# USB.net
KiCad netlist of a schematic drawn in Altium Designer
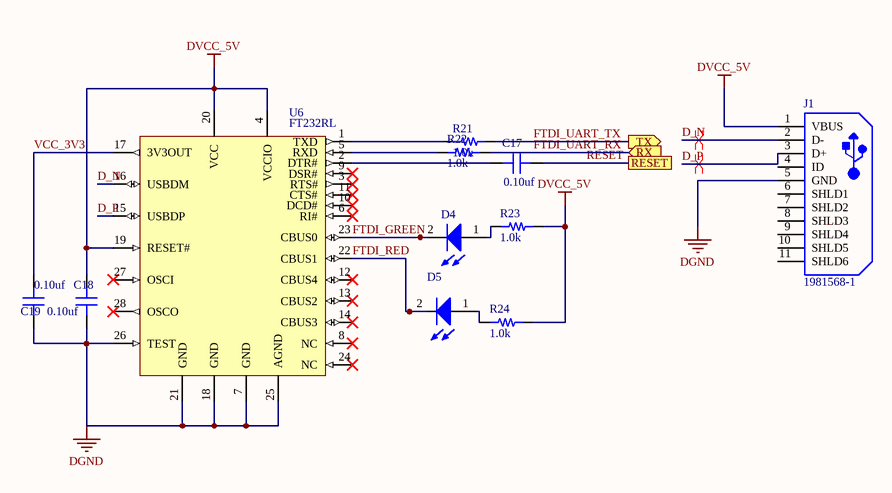
[diagram p0: USB.SchDoc]

(export (version "E")
  (design (tool "Eeschema 10.0.6"))
  (components
    (comp (ref "C17")
      (value "0.10uf")
      (footprint "CAP 0603/1608")
      (fields
        (field (name "Comment") "Capacitor MLCC 0.10uf 25V CAP 0603/1608")
        (field (name "CREATED_BY") "Nick Mah")
      )
      (libsource (lib "Altium-Lib") (part "Capacitor"))
    )
    (comp (ref "C18")
      (value "0.10uf")
      (footprint "CAP 0603/1608")
      (fields
        (field (name "Comment") "Capacitor MLCC 0.10uf 25V CAP 0603/1608")
        (field (name "CREATED_BY") "Nick Mah")
      )
      (libsource (lib "Altium-Lib") (part "Capacitor"))
    )
    (comp (ref "C19")
      (value "0.10uf")
      (footprint "CAP 0603/1608")
      (fields
        (field (name "Comment") "Capacitor MLCC 0.10uf 25V CAP 0603/1608")
        (field (name "CREATED_BY") "Nick Mah")
      )
      (libsource (lib "Altium-Lib") (part "Capacitor"))
    )
    (comp (ref "D4") (value "~") (footprint "0805_LED") (libsource (lib "Altium-Lib") (part "LED")))
    (comp (ref "D5") (value "~") (footprint "0805_LED") (libsource (lib "Altium-Lib") (part "LED")))
    (comp (ref "J1")
      (value "1981568-1")
      (footprint "TECO-1981568-5_V")
      (description "USB Micro Type B")
      (fields (field (name "CREATED_BY") "Aiku"))
      (libsource (lib "Altium-Lib") (part "USB-5-6SHLD"))
    )
    (comp (ref "R21")
      (value "1.0k")
      (footprint "RES 0603/1608")
      (fields
        (field (name "TOLERANCE") "5%")
        (field (name "POWER") "1/10W")
        (field (name "Comment") "Resistor 1.0k 0603 1/10W 5%")
        (field (name "CREATED_BY") "Nick Mah")
      )
      (libsource (lib "Altium-Lib") (part "Resistor"))
    )
    (comp (ref "R22")
      (value "1.0k")
      (footprint "RES 0603/1608")
      (fields
        (field (name "TOLERANCE") "5%")
        (field (name "POWER") "1/10W")
        (field (name "Comment") "Resistor 1.0k 0603 1/10W 5%")
        (field (name "CREATED_BY") "Nick Mah")
      )
      (libsource (lib "Altium-Lib") (part "Resistor"))
    )
    (comp (ref "R23")
      (value "1.0k")
      (footprint "RES 0603/1608")
      (fields
        (field (name "TOLERANCE") "5%")
        (field (name "POWER") "1/10W")
        (field (name "Comment") "Resistor 1.0k 0603 1/10W 5%")
        (field (name "CREATED_BY") "Nick Mah")
      )
      (libsource (lib "Altium-Lib") (part "Resistor"))
    )
    (comp (ref "R24")
      (value "1.0k")
      (footprint "RES 0603/1608")
      (fields
        (field (name "TOLERANCE") "5%")
        (field (name "POWER") "1/10W")
        (field (name "Comment") "Resistor 1.0k 0603 1/10W 5%")
        (field (name "CREATED_BY") "Nick Mah")
      )
      (libsource (lib "Altium-Lib") (part "Resistor"))
    )
    (comp (ref "U6")
      (value "FT232RL")
      (footprint "SSOP-28")
      (fields (field (name "CREATED_BY") "Kyle"))
      (libsource (lib "Altium-Lib") (part "FT232RL"))
    )
  )
  (nets
    (net (code "1") (name "/D_N") (class "Default")
      (node (ref "J1") (pin "2") (pinfunction "D-_2") (pintype "passive"))
      (node (ref "U6") (pin "16") (pinfunction "USBDM_16") (pintype "bidirectional"))
    )
    (net (code "2") (name "/D_P") (class "Default")
      (node (ref "J1") (pin "3") (pinfunction "D+_3") (pintype "passive"))
      (node (ref "U6") (pin "15") (pinfunction "USBDP_15") (pintype "bidirectional"))
    )
    (net (code "3") (name "/FTDI_GREEN") (class "Default")
      (node (ref "D4") (pin "2") (pinfunction "K_2") (pintype "passive"))
      (node (ref "U6") (pin "23") (pinfunction "CBUS0_23") (pintype "bidirectional"))
    )
    (net (code "4") (name "/FTDI_RED") (class "Default")
      (node (ref "D5") (pin "2") (pinfunction "K_2") (pintype "passive"))
      (node (ref "U6") (pin "22") (pinfunction "CBUS1_22") (pintype "bidirectional"))
    )
    (net (code "5") (name "/FTDI_UART_RX") (class "Default")
      (node (ref "R22") (pin "2") (pinfunction "2_2") (pintype "passive"))
    )
    (net (code "6") (name "/FTDI_UART_TX") (class "Default")
      (node (ref "R21") (pin "2") (pinfunction "2_2") (pintype "passive"))
    )
    (net (code "7") (name "/RESET") (class "Default")
      (node (ref "C17") (pin "2") (pinfunction "2_2") (pintype "passive"))
    )
    (net (code "8") (name "/VCC_3V3") (class "Default")
      (node (ref "C19") (pin "2") (pinfunction "2_2") (pintype "passive"))
      (node (ref "U6") (pin "17") (pinfunction "3V3OUT_17") (pintype "output"))
    )
    (net (code "9") (name "DGND") (class "Default")
      (node (ref "C18") (pin "1") (pinfunction "1_1") (pintype "passive"))
      (node (ref "C19") (pin "1") (pinfunction "1_1") (pintype "passive"))
      (node (ref "J1") (pin "5") (pinfunction "GND_5") (pintype "passive"))
      (node (ref "U6") (pin "18") (pinfunction "GND_18") (pintype "passive"))
      (node (ref "U6") (pin "21") (pinfunction "GND_21") (pintype "passive"))
      (node (ref "U6") (pin "25") (pinfunction "AGND_25") (pintype "passive"))
      (node (ref "U6") (pin "26") (pinfunction "TEST_26") (pintype "input"))
      (node (ref "U6") (pin "7") (pinfunction "GND_7") (pintype "passive"))
    )
    (net (code "10") (name "DVCC_5V") (class "Default")
      (node (ref "C18") (pin "2") (pinfunction "2_2") (pintype "passive"))
      (node (ref "J1") (pin "1") (pinfunction "VBUS_1") (pintype "passive"))
      (node (ref "R23") (pin "2") (pinfunction "2_2") (pintype "passive"))
      (node (ref "R24") (pin "2") (pinfunction "2_2") (pintype "passive"))
      (node (ref "U6") (pin "19") (pinfunction "RESET#_19") (pintype "input"))
      (node (ref "U6") (pin "20") (pinfunction "VCC_20") (pintype "passive"))
      (node (ref "U6") (pin "4") (pinfunction "VCCIO_4") (pintype "passive"))
    )
    (net (code "11") (name "Net-(D4-A)") (class "Default")
      (node (ref "D4") (pin "1") (pinfunction "A_1") (pintype "passive"))
      (node (ref "R23") (pin "1") (pinfunction "1_1") (pintype "passive"))
    )
    (net (code "12") (name "Net-(D5-A)") (class "Default")
      (node (ref "D5") (pin "1") (pinfunction "A_1") (pintype "passive"))
      (node (ref "R24") (pin "1") (pinfunction "1_1") (pintype "passive"))
    )
    (net (code "13") (name "Net-(U6-DTR#)") (class "Default")
      (node (ref "C17") (pin "1") (pinfunction "1_1") (pintype "passive"))
      (node (ref "U6") (pin "2") (pinfunction "DTR#_2") (pintype "output"))
    )
    (net (code "14") (name "Net-(U6-RXD)") (class "Default")
      (node (ref "R22") (pin "1") (pinfunction "1_1") (pintype "passive"))
      (node (ref "U6") (pin "5") (pinfunction "RXD_5") (pintype "input"))
    )
    (net (code "15") (name "Net-(U6-TXD)") (class "Default")
      (node (ref "R21") (pin "1") (pinfunction "1_1") (pintype "passive"))
      (node (ref "U6") (pin "1") (pinfunction "TXD_1") (pintype "output"))
    )
    (net (code "16") (name "unconnected-(J1-ID-Pad4)") (class "Default")
      (node (ref "J1") (pin "4") (pinfunction "ID_4") (pintype "passive"))
    )
    (net (code "17") (name "unconnected-(J1-SHLD1-Pad6)") (class "Default")
      (node (ref "J1") (pin "6") (pinfunction "SHLD1_6") (pintype "passive"))
    )
    (net (code "18") (name "unconnected-(J1-SHLD2-Pad7)") (class "Default")
      (node (ref "J1") (pin "7") (pinfunction "SHLD2_7") (pintype "passive"))
    )
    (net (code "19") (name "unconnected-(J1-SHLD3-Pad8)") (class "Default")
      (node (ref "J1") (pin "8") (pinfunction "SHLD3_8") (pintype "passive"))
    )
    (net (code "20") (name "unconnected-(J1-SHLD4-Pad9)") (class "Default")
      (node (ref "J1") (pin "9") (pinfunction "SHLD4_9") (pintype "passive"))
    )
    (net (code "21") (name "unconnected-(J1-SHLD5-Pad10)") (class "Default")
      (node (ref "J1") (pin "10") (pinfunction "SHLD5_10") (pintype "passive"))
    )
    (net (code "22") (name "unconnected-(J1-SHLD6-Pad11)") (class "Default")
      (node (ref "J1") (pin "11") (pinfunction "SHLD6_11") (pintype "passive"))
    )
    (net (code "23") (name "unconnected-(U6-CBUS2-Pad13)") (class "Default")
      (node (ref "U6") (pin "13") (pinfunction "CBUS2_13") (pintype "bidirectional+no_connect"))
    )
    (net (code "24") (name "unconnected-(U6-CBUS3-Pad14)") (class "Default")
      (node (ref "U6") (pin "14") (pinfunction "CBUS3_14") (pintype "bidirectional+no_connect"))
    )
    (net (code "25") (name "unconnected-(U6-CBUS4-Pad12)") (class "Default")
      (node (ref "U6") (pin "12") (pinfunction "CBUS4_12") (pintype "bidirectional+no_connect"))
    )
    (net (code "26") (name "unconnected-(U6-CTS#-Pad11)") (class "Default")
      (node (ref "U6") (pin "11") (pinfunction "CTS#_11") (pintype "input+no_connect"))
    )
    (net (code "27") (name "unconnected-(U6-DCD#-Pad10)") (class "Default")
      (node (ref "U6") (pin "10") (pinfunction "DCD#_10") (pintype "input+no_connect"))
    )
    (net (code "28") (name "unconnected-(U6-DSR#-Pad9)") (class "Default")
      (node (ref "U6") (pin "9") (pinfunction "DSR#_9") (pintype "input+no_connect"))
    )
    (net (code "29") (name "unconnected-(U6-NC-Pad8)") (class "Default")
      (node (ref "U6") (pin "8") (pinfunction "NC_8") (pintype "input+no_connect"))
    )
    (net (code "30") (name "unconnected-(U6-NC-Pad24)") (class "Default")
      (node (ref "U6") (pin "24") (pinfunction "NC_24") (pintype "input+no_connect"))
    )
    (net (code "31") (name "unconnected-(U6-OSCI-Pad27)") (class "Default")
      (node (ref "U6") (pin "27") (pinfunction "OSCI_27") (pintype "input+no_connect"))
    )
    (net (code "32") (name "unconnected-(U6-OSCO-Pad28)") (class "Default")
      (node (ref "U6") (pin "28") (pinfunction "OSCO_28") (pintype "output+no_connect"))
    )
    (net (code "33") (name "unconnected-(U6-RI#-Pad6)") (class "Default")
      (node (ref "U6") (pin "6") (pinfunction "RI#_6") (pintype "input+no_connect"))
    )
    (net (code "34") (name "unconnected-(U6-RTS#-Pad3)") (class "Default")
      (node (ref "U6") (pin "3") (pinfunction "RTS#_3") (pintype "output+no_connect"))
    )
  )
)
